# MCU.net
KiCad netlist of a schematic drawn in Altium Designer
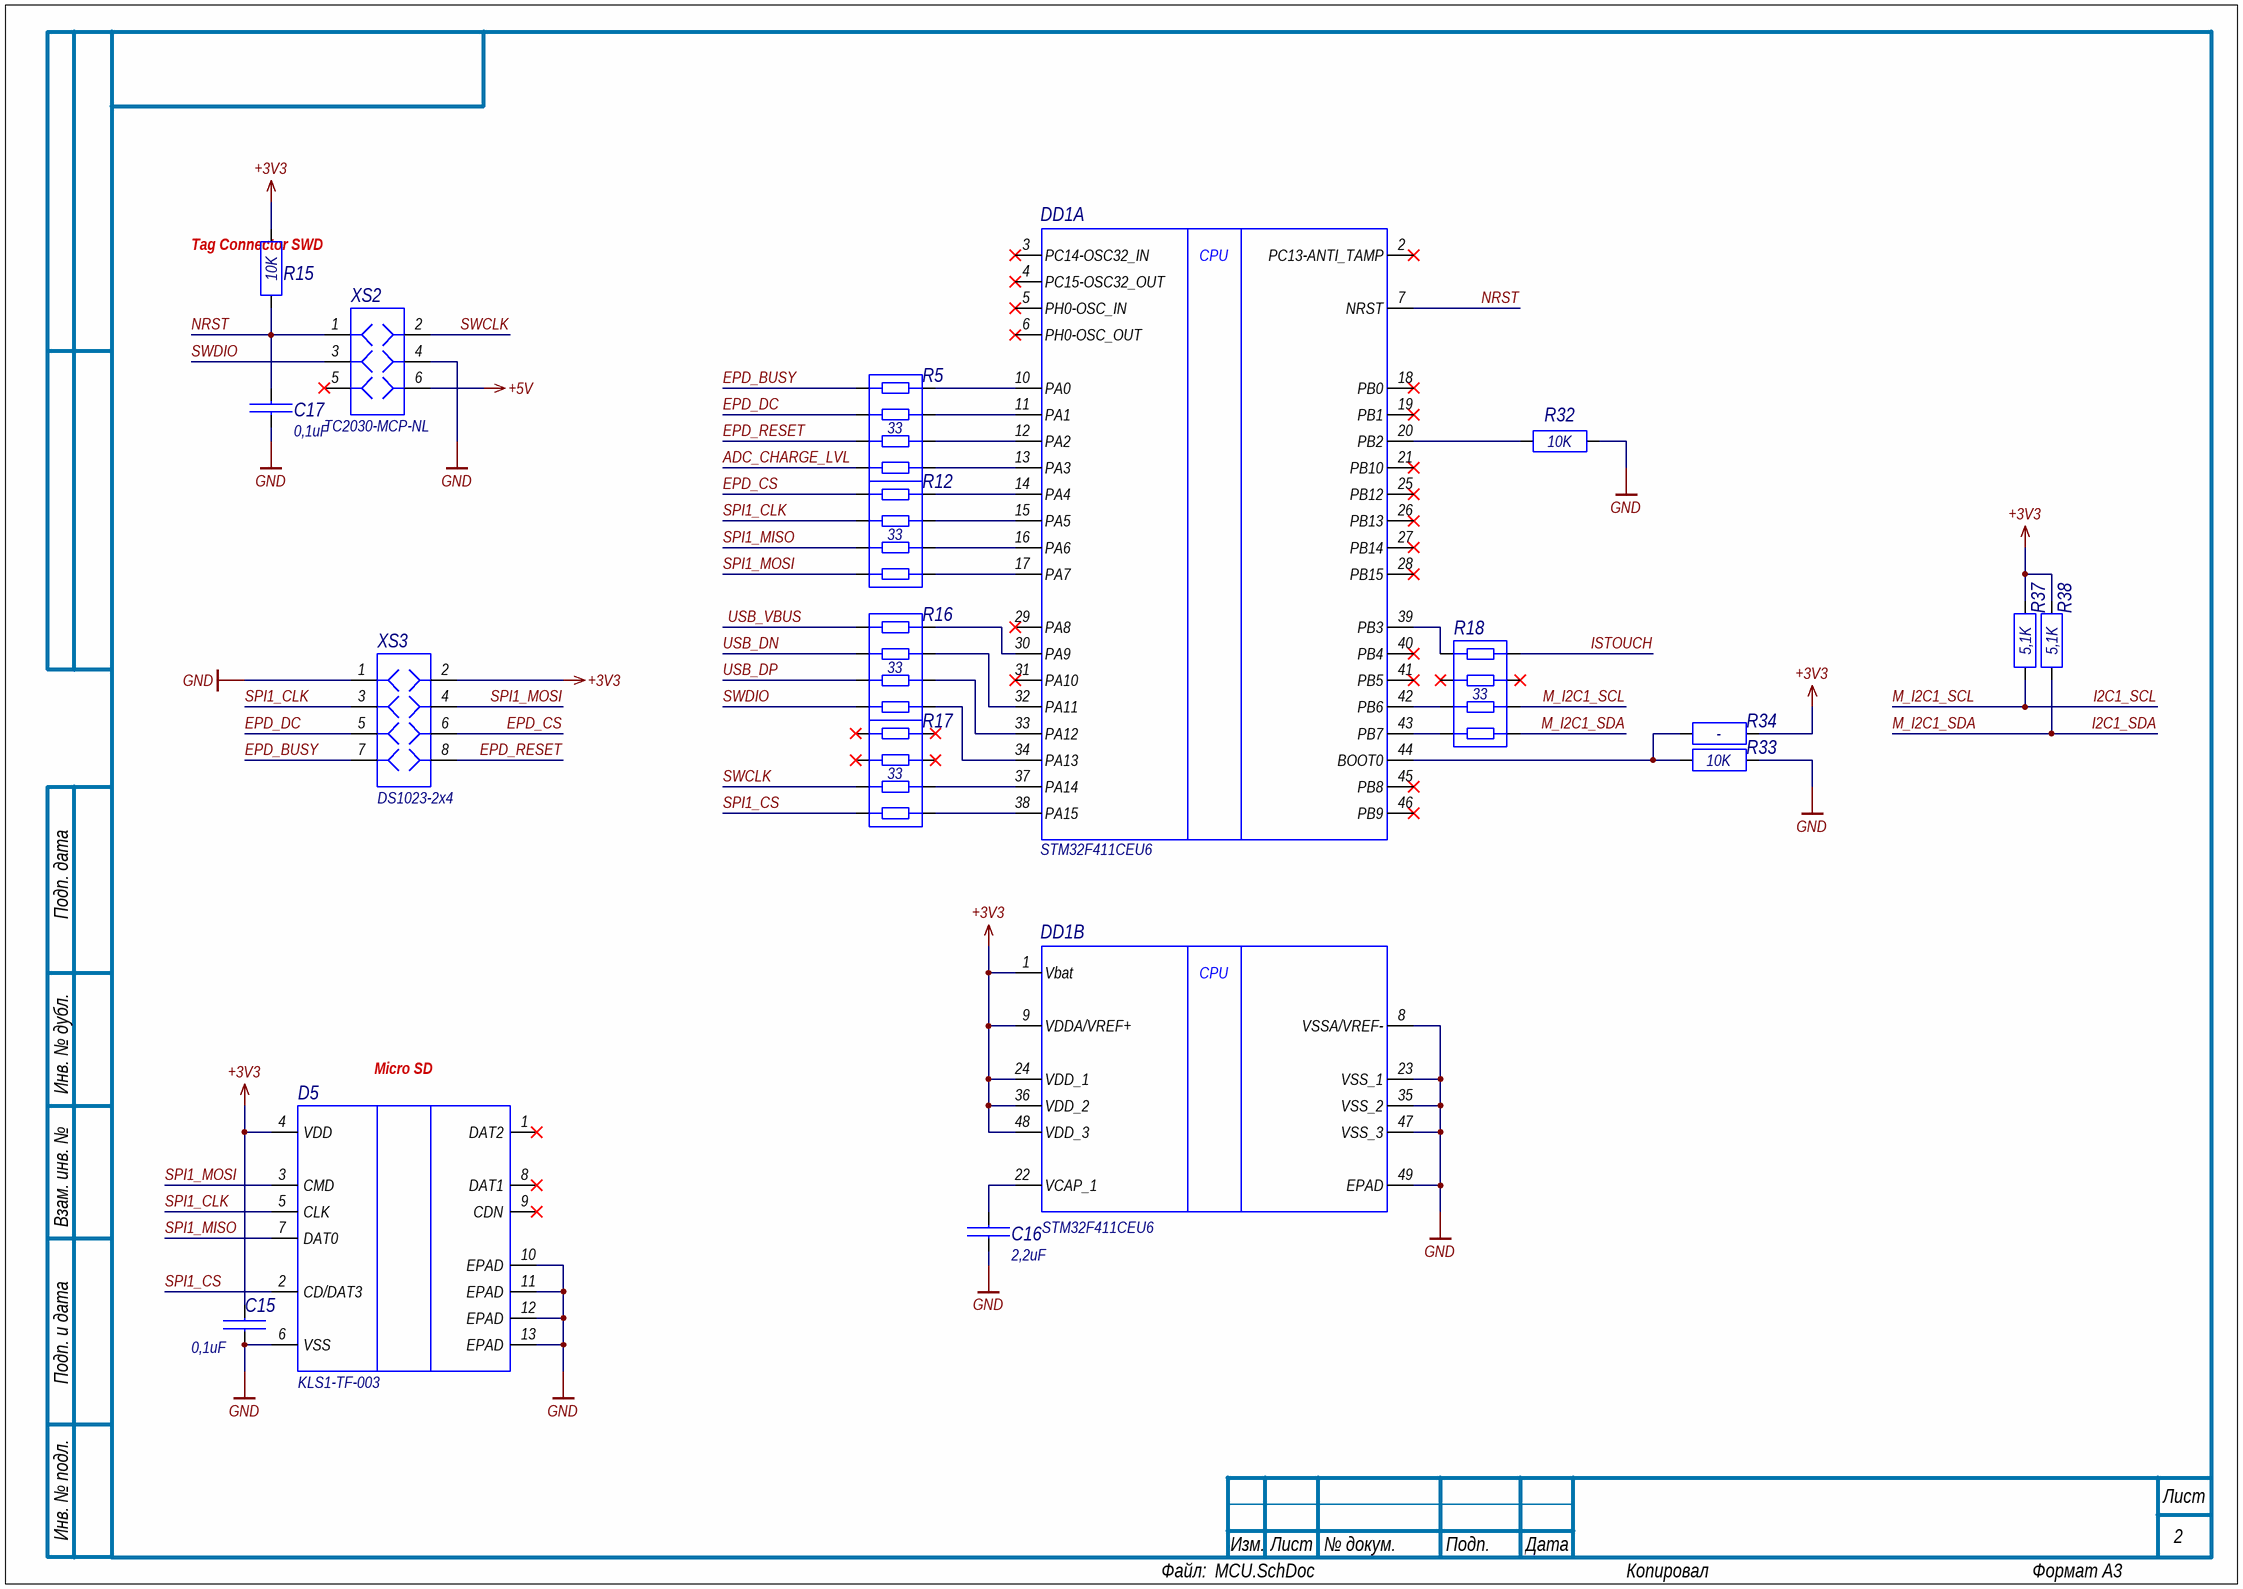
[diagram p0: MCU.SchDoc]

(export (version "E")
  (design (tool "Eeschema 10.0.6"))
  (components
    (comp (ref "C15")
      (value "0,1uF")
      (footprint "CAP_0603")
      (description "Ceramic Capacitor SMD_0603 X7R")
      (fields (field (name "VOLTAGE") "25V") (field (name "PART NUMBER") "CAP_CER_0603_104_25_10_X7R"))
      (libsource (lib "myLib_ESKD") (part "CAPACITOR"))
    )
    (comp (ref "C16")
      (value "2,2uF")
      (footprint "CAP_0603")
      (description "Ceramic Capacitor SMD_0603 X5R")
      (fields (field (name "VOLTAGE") "10V") (field (name "PART NUMBER") "CAP_CER_0603_225_10_10_X5R"))
      (libsource (lib "myLib_ESKD") (part "CAPACITOR"))
    )
    (comp (ref "C17")
      (value "0,1uF")
      (footprint "CAP_0603")
      (description "Ceramic Capacitor SMD_0603 X7R")
      (fields (field (name "VOLTAGE") "25V") (field (name "PART NUMBER") "CAP_CER_0603_104_25_10_X7R"))
      (libsource (lib "myLib_ESKD") (part "CAPACITOR"))
    )
    (comp (ref "D5")
      (value "KLS1-TF-003")
      (footprint "KLS1-TF-003")
      (description "microSD Card Connector")
      (fields (field (name "MANUFACTURER") "KLS"))
      (libsource (lib "myLib_ESKD") (part "KLS1-TF-003"))
    )
    (comp (ref "DD1")
      (value "STM32F411CEU6")
      (footprint "UFQFPN48")
      (fields
        (field (name "MOUSER PART NUMBER") "511-STM32F411CEU6")
        (field (name "MANUFACTURER") "STMicroelectronics")
      )
      (libsource (lib "myLib_ESKD") (part "STM32F411CEU6"))
    )
    (comp (ref "R5")
      (value "33")
      (footprint "RES_ARRAY_0804_CONVEX")
      (description "CAY10 Series - Chip Resistor Array")
      (fields (field (name "PART NUMBER") "RES_ARR_CAY10_33R") (field (name "TOLERANCE") "5%"))
      (libsource (lib "myLib_ESKD") (part "RESISTOR_ARRAY"))
    )
    (comp (ref "R12")
      (value "33")
      (footprint "RES_ARRAY_0804_CONVEX")
      (description "CAY10 Series - Chip Resistor Array")
      (fields (field (name "PART NUMBER") "RES_ARR_CAY10_33R") (field (name "TOLERANCE") "5%"))
      (libsource (lib "myLib_ESKD") (part "RESISTOR_ARRAY"))
    )
    (comp (ref "R15")
      (value "10K")
      (footprint "RES_0603")
      (description "Resistor fixed SMD_0603 5%")
      (fields (field (name "POWER") "100mW") (field (name "PART NUMBER") "RES_SMD_0603_10K_5%"))
      (libsource (lib "myLib_ESKD") (part "RESISTOR"))
    )
    (comp (ref "R16")
      (value "33")
      (footprint "RES_ARRAY_0804_CONVEX")
      (description "CAY10 Series - Chip Resistor Array")
      (fields (field (name "PART NUMBER") "RES_ARR_CAY10_33R") (field (name "TOLERANCE") "5%"))
      (libsource (lib "myLib_ESKD") (part "RESISTOR_ARRAY"))
    )
    (comp (ref "R17")
      (value "33")
      (footprint "RES_ARRAY_0804_CONVEX")
      (description "CAY10 Series - Chip Resistor Array")
      (fields (field (name "PART NUMBER") "RES_ARR_CAY10_33R") (field (name "TOLERANCE") "5%"))
      (libsource (lib "myLib_ESKD") (part "RESISTOR_ARRAY"))
    )
    (comp (ref "R18")
      (value "33")
      (footprint "RES_ARRAY_0804_CONVEX")
      (description "CAY10 Series - Chip Resistor Array")
      (fields (field (name "PART NUMBER") "RES_ARR_CAY10_33R") (field (name "TOLERANCE") "5%"))
      (libsource (lib "myLib_ESKD") (part "RESISTOR_ARRAY"))
    )
    (comp (ref "R32")
      (value "10K")
      (footprint "RES_0603")
      (description "Resistor fixed SMD_0603 5%")
      (fields (field (name "POWER") "100mW") (field (name "PART NUMBER") "RES_SMD_0603_10K_5%"))
      (libsource (lib "myLib_ESKD") (part "RESISTOR"))
    )
    (comp (ref "R33")
      (value "10K")
      (footprint "RES_0603")
      (description "Resistor fixed SMD_0603 5%")
      (fields (field (name "POWER") "100mW") (field (name "PART NUMBER") "RES_SMD_0603_10K_5%"))
      (libsource (lib "myLib_ESKD") (part "RESISTOR"))
    )
    (comp (ref "R34")
      (value "-")
      (footprint "RES_0603")
      (description "Resistor fixed SMD_0603 5%")
      (fields (field (name "POWER") "100mW") (field (name "PART NUMBER") "RES_SMD_0603_10K_5%"))
      (libsource (lib "myLib_ESKD") (part "RESISTOR"))
    )
    (comp (ref "R37")
      (value "5,1K")
      (footprint "RES_0603")
      (description "Resistor fixed SMD_0603 5%")
      (fields (field (name "POWER") "100mW") (field (name "PART NUMBER") "RES_SMD_0603_5K1_5%"))
      (libsource (lib "myLib_ESKD") (part "RESISTOR"))
    )
    (comp (ref "R38")
      (value "5,1K")
      (footprint "RES_0603")
      (description "Resistor fixed SMD_0603 5%")
      (fields (field (name "POWER") "100mW") (field (name "PART NUMBER") "RES_SMD_0603_5K1_5%"))
      (libsource (lib "myLib_ESKD") (part "RESISTOR"))
    )
    (comp (ref "XS2")
      (value "TC2030-MCP-NL")
      (footprint "TC2030-MCP-NL")
      (description "Tag connector 2x3")
      (fields (field (name "MANUFACTURER") "Tag Connect") (field (name "Comment") "HEADER-3x2-F"))
      (libsource (lib "myLib_ESKD") (part "HEADER-3x2-F"))
    )
    (comp (ref "XS3")
      (value "DS1023-2x4")
      (footprint "PBD-8")
      (description "Female Socket Header Through Hole 8 (2x4) Position 0.100\" (2.54mm)")
      (fields (field (name "PART NUMBER") "PBD-8") (field (name "MANUFACTURER") "Connfly"))
      (libsource (lib "myLib_ESKD") (part "HEADER-4x2-F"))
    )
  )
  (nets
    (net (code "1") (name "+3V3") (class "Default")
      (node (ref "C15") (pin "1") (pinfunction "1_1") (pintype "passive"))
      (node (ref "D5") (pin "4") (pinfunction "VDD_4") (pintype "passive"))
      (node (ref "DD1") (pin "1") (pinfunction "Vbat_1") (pintype "passive"))
      (node (ref "DD1") (pin "24") (pinfunction "VDD_1_24") (pintype "passive"))
      (node (ref "DD1") (pin "36") (pinfunction "VDD_2_36") (pintype "passive"))
      (node (ref "DD1") (pin "48") (pinfunction "VDD_3_48") (pintype "passive"))
      (node (ref "DD1") (pin "9") (pinfunction "VDDA/VREF+_9") (pintype "passive"))
      (node (ref "R15") (pin "2") (pinfunction "2_2") (pintype "passive"))
      (node (ref "R34") (pin "2") (pinfunction "2_2") (pintype "passive"))
      (node (ref "R37") (pin "2") (pinfunction "2_2") (pintype "passive"))
      (node (ref "R38") (pin "2") (pinfunction "2_2") (pintype "passive"))
      (node (ref "XS3") (pin "2") (pinfunction "2_2") (pintype "passive"))
    )
    (net (code "2") (name "+5V") (class "Default")
      (node (ref "XS2") (pin "6") (pinfunction "6_6") (pintype "passive"))
    )
    (net (code "3") (name "/ADC_CHARGE_LVL") (class "Default")
      (node (ref "R5") (pin "4") (pinfunction "4_4") (pintype "passive"))
    )
    (net (code "4") (name "/EPD_BUSY") (class "Default")
      (node (ref "R5") (pin "1") (pinfunction "1_1") (pintype "passive"))
      (node (ref "XS3") (pin "7") (pinfunction "7_7") (pintype "passive"))
    )
    (net (code "5") (name "/EPD_CS") (class "Default")
      (node (ref "R12") (pin "1") (pinfunction "1_1") (pintype "passive"))
      (node (ref "XS3") (pin "6") (pinfunction "6_6") (pintype "passive"))
    )
    (net (code "6") (name "/EPD_DC") (class "Default")
      (node (ref "R5") (pin "2") (pinfunction "2_2") (pintype "passive"))
      (node (ref "XS3") (pin "5") (pinfunction "5_5") (pintype "passive"))
    )
    (net (code "7") (name "/EPD_RESET") (class "Default")
      (node (ref "R5") (pin "3") (pinfunction "3_3") (pintype "passive"))
      (node (ref "XS3") (pin "8") (pinfunction "8_8") (pintype "passive"))
    )
    (net (code "8") (name "/I2C1_SCL") (class "Default")
      (node (ref "R18") (pin "7") (pinfunction "7_7") (pintype "passive"))
      (node (ref "R37") (pin "1") (pinfunction "1_1") (pintype "passive"))
    )
    (net (code "9") (name "/I2C1_SDA") (class "Default")
      (node (ref "R18") (pin "8") (pinfunction "8_8") (pintype "passive"))
      (node (ref "R38") (pin "1") (pinfunction "1_1") (pintype "passive"))
    )
    (net (code "10") (name "/ISTOUCH") (class "Default")
      (node (ref "R18") (pin "5") (pinfunction "5_5") (pintype "passive"))
    )
    (net (code "11") (name "/NRST") (class "Default")
      (node (ref "C17") (pin "1") (pinfunction "1_1") (pintype "passive"))
      (node (ref "DD1") (pin "7") (pinfunction "NRST_7") (pintype "passive"))
      (node (ref "R15") (pin "1") (pinfunction "1_1") (pintype "passive"))
      (node (ref "XS2") (pin "1") (pinfunction "1_1") (pintype "passive"))
    )
    (net (code "12") (name "/SPI1_CLK") (class "Default")
      (node (ref "D5") (pin "5") (pinfunction "CLK_5") (pintype "passive"))
      (node (ref "R12") (pin "2") (pinfunction "2_2") (pintype "passive"))
      (node (ref "XS3") (pin "3") (pinfunction "3_3") (pintype "passive"))
    )
    (net (code "13") (name "/SPI1_CS") (class "Default")
      (node (ref "D5") (pin "2") (pinfunction "CD/DAT3_2") (pintype "passive"))
      (node (ref "R17") (pin "4") (pinfunction "4_4") (pintype "passive"))
    )
    (net (code "14") (name "/SPI1_MISO") (class "Default")
      (node (ref "D5") (pin "7") (pinfunction "DAT0_7") (pintype "passive"))
      (node (ref "R12") (pin "3") (pinfunction "3_3") (pintype "passive"))
    )
    (net (code "15") (name "/SPI1_MOSI") (class "Default")
      (node (ref "D5") (pin "3") (pinfunction "CMD_3") (pintype "passive"))
      (node (ref "R12") (pin "4") (pinfunction "4_4") (pintype "passive"))
      (node (ref "XS3") (pin "4") (pinfunction "4_4") (pintype "passive"))
    )
    (net (code "16") (name "/SWCLK") (class "Default")
      (node (ref "R17") (pin "3") (pinfunction "3_3") (pintype "passive"))
      (node (ref "XS2") (pin "2") (pinfunction "2_2") (pintype "passive"))
    )
    (net (code "17") (name "/SWDIO") (class "Default")
      (node (ref "R16") (pin "4") (pinfunction "4_4") (pintype "passive"))
      (node (ref "XS2") (pin "3") (pinfunction "3_3") (pintype "passive"))
    )
    (net (code "18") (name "/USB_DN") (class "Default")
      (node (ref "R16") (pin "2") (pinfunction "2_2") (pintype "passive"))
    )
    (net (code "19") (name "/USB_DP") (class "Default")
      (node (ref "R16") (pin "3") (pinfunction "3_3") (pintype "passive"))
    )
    (net (code "20") (name "/USB_VBUS") (class "Default")
      (node (ref "R16") (pin "1") (pinfunction "1_1") (pintype "passive"))
    )
    (net (code "21") (name "GND") (class "Default")
      (node (ref "C15") (pin "2") (pinfunction "2_2") (pintype "passive"))
      (node (ref "C16") (pin "2") (pinfunction "2_2") (pintype "passive"))
      (node (ref "C17") (pin "2") (pinfunction "2_2") (pintype "passive"))
      (node (ref "D5") (pin "10") (pinfunction "EPAD_10") (pintype "passive"))
      (node (ref "D5") (pin "11") (pinfunction "EPAD_11") (pintype "passive"))
      (node (ref "D5") (pin "12") (pinfunction "EPAD_12") (pintype "passive"))
      (node (ref "D5") (pin "13") (pinfunction "EPAD_13") (pintype "passive"))
      (node (ref "D5") (pin "6") (pinfunction "VSS_6") (pintype "passive"))
      (node (ref "DD1") (pin "23") (pinfunction "VSS_1_23") (pintype "passive"))
      (node (ref "DD1") (pin "35") (pinfunction "VSS_2_35") (pintype "passive"))
      (node (ref "DD1") (pin "47") (pinfunction "VSS_3_47") (pintype "passive"))
      (node (ref "DD1") (pin "49") (pinfunction "EPAD_49") (pintype "passive"))
      (node (ref "DD1") (pin "8") (pinfunction "VSSA/VREF-_8") (pintype "passive"))
      (node (ref "R32") (pin "2") (pinfunction "2_2") (pintype "passive"))
      (node (ref "R33") (pin "2") (pinfunction "2_2") (pintype "passive"))
      (node (ref "XS2") (pin "4") (pinfunction "4_4") (pintype "passive"))
      (node (ref "XS3") (pin "1") (pinfunction "1_1") (pintype "passive"))
    )
    (net (code "22") (name "Net-(DD1A-BOOT0)") (class "Default")
      (node (ref "DD1") (pin "44") (pinfunction "BOOT0_44") (pintype "passive"))
      (node (ref "R33") (pin "1") (pinfunction "1_1") (pintype "passive"))
      (node (ref "R34") (pin "1") (pinfunction "1_1") (pintype "passive"))
    )
    (net (code "23") (name "Net-(DD1A-PA0)") (class "Default")
      (node (ref "DD1") (pin "10") (pinfunction "PA0_10") (pintype "passive"))
      (node (ref "R5") (pin "8") (pinfunction "8_8") (pintype "passive"))
    )
    (net (code "24") (name "Net-(DD1A-PA1)") (class "Default")
      (node (ref "DD1") (pin "11") (pinfunction "PA1_11") (pintype "passive"))
      (node (ref "R5") (pin "7") (pinfunction "7_7") (pintype "passive"))
    )
    (net (code "25") (name "Net-(DD1A-PA2)") (class "Default")
      (node (ref "DD1") (pin "12") (pinfunction "PA2_12") (pintype "passive"))
      (node (ref "R5") (pin "6") (pinfunction "6_6") (pintype "passive"))
    )
    (net (code "26") (name "Net-(DD1A-PA3)") (class "Default")
      (node (ref "DD1") (pin "13") (pinfunction "PA3_13") (pintype "passive"))
      (node (ref "R5") (pin "5") (pinfunction "5_5") (pintype "passive"))
    )
    (net (code "27") (name "Net-(DD1A-PA4)") (class "Default")
      (node (ref "DD1") (pin "14") (pinfunction "PA4_14") (pintype "passive"))
      (node (ref "R12") (pin "8") (pinfunction "8_8") (pintype "passive"))
    )
    (net (code "28") (name "Net-(DD1A-PA5)") (class "Default")
      (node (ref "DD1") (pin "15") (pinfunction "PA5_15") (pintype "passive"))
      (node (ref "R12") (pin "7") (pinfunction "7_7") (pintype "passive"))
    )
    (net (code "29") (name "Net-(DD1A-PA6)") (class "Default")
      (node (ref "DD1") (pin "16") (pinfunction "PA6_16") (pintype "passive"))
      (node (ref "R12") (pin "6") (pinfunction "6_6") (pintype "passive"))
    )
    (net (code "30") (name "Net-(DD1A-PA7)") (class "Default")
      (node (ref "DD1") (pin "17") (pinfunction "PA7_17") (pintype "passive"))
      (node (ref "R12") (pin "5") (pinfunction "5_5") (pintype "passive"))
    )
    (net (code "31") (name "Net-(DD1A-PA9)") (class "Default")
      (node (ref "DD1") (pin "30") (pinfunction "PA9_30") (pintype "passive"))
      (node (ref "R16") (pin "8") (pinfunction "8_8") (pintype "passive"))
    )
    (net (code "32") (name "Net-(DD1A-PA11)") (class "Default")
      (node (ref "DD1") (pin "32") (pinfunction "PA11_32") (pintype "passive"))
      (node (ref "R16") (pin "7") (pinfunction "7_7") (pintype "passive"))
    )
    (net (code "33") (name "Net-(DD1A-PA12)") (class "Default")
      (node (ref "DD1") (pin "33") (pinfunction "PA12_33") (pintype "passive"))
      (node (ref "R16") (pin "6") (pinfunction "6_6") (pintype "passive"))
    )
    (net (code "34") (name "Net-(DD1A-PA13)") (class "Default")
      (node (ref "DD1") (pin "34") (pinfunction "PA13_34") (pintype "passive"))
      (node (ref "R16") (pin "5") (pinfunction "5_5") (pintype "passive"))
    )
    (net (code "35") (name "Net-(DD1A-PA14)") (class "Default")
      (node (ref "DD1") (pin "37") (pinfunction "PA14_37") (pintype "passive"))
      (node (ref "R17") (pin "6") (pinfunction "6_6") (pintype "passive"))
    )
    (net (code "36") (name "Net-(DD1A-PA15)") (class "Default")
      (node (ref "DD1") (pin "38") (pinfunction "PA15_38") (pintype "passive"))
      (node (ref "R17") (pin "5") (pinfunction "5_5") (pintype "passive"))
    )
    (net (code "37") (name "Net-(DD1A-PB2)") (class "Default")
      (node (ref "DD1") (pin "20") (pinfunction "PB2_20") (pintype "passive"))
      (node (ref "R32") (pin "1") (pinfunction "1_1") (pintype "passive"))
    )
    (net (code "38") (name "Net-(DD1A-PB3)") (class "Default")
      (node (ref "DD1") (pin "39") (pinfunction "PB3_39") (pintype "passive"))
      (node (ref "R18") (pin "4") (pinfunction "4_4") (pintype "passive"))
    )
    (net (code "39") (name "Net-(DD1A-PB6)") (class "Default")
      (node (ref "DD1") (pin "42") (pinfunction "PB6_42") (pintype "passive"))
      (node (ref "R18") (pin "2") (pinfunction "2_2") (pintype "passive"))
    )
    (net (code "40") (name "Net-(DD1A-PB7)") (class "Default")
      (node (ref "DD1") (pin "43") (pinfunction "PB7_43") (pintype "passive"))
      (node (ref "R18") (pin "1") (pinfunction "1_1") (pintype "passive"))
    )
    (net (code "41") (name "Net-(DD1B-VCAP_1)") (class "Default")
      (node (ref "C16") (pin "1") (pinfunction "1_1") (pintype "passive"))
      (node (ref "DD1") (pin "22") (pinfunction "VCAP_1_22") (pintype "passive"))
    )
    (net (code "42") (name "unconnected-(D5-CDN-Pad9)") (class "Default")
      (node (ref "D5") (pin "9") (pinfunction "CDN_9") (pintype "passive+no_connect"))
    )
    (net (code "43") (name "unconnected-(D5-DAT1-Pad8)") (class "Default")
      (node (ref "D5") (pin "8") (pinfunction "DAT1_8") (pintype "passive+no_connect"))
    )
    (net (code "44") (name "unconnected-(D5-DAT2-Pad1)") (class "Default")
      (node (ref "D5") (pin "1") (pinfunction "DAT2_1") (pintype "passive+no_connect"))
    )
    (net (code "45") (name "unconnected-(DD1A-PA8-Pad29)") (class "Default")
      (node (ref "DD1") (pin "29") (pinfunction "PA8_29") (pintype "passive+no_connect"))
    )
    (net (code "46") (name "unconnected-(DD1A-PA10-Pad31)") (class "Default")
      (node (ref "DD1") (pin "31") (pinfunction "PA10_31") (pintype "passive+no_connect"))
    )
    (net (code "47") (name "unconnected-(DD1A-PB0-Pad18)") (class "Default")
      (node (ref "DD1") (pin "18") (pinfunction "PB0_18") (pintype "passive+no_connect"))
    )
    (net (code "48") (name "unconnected-(DD1A-PB1-Pad19)") (class "Default")
      (node (ref "DD1") (pin "19") (pinfunction "PB1_19") (pintype "passive+no_connect"))
    )
    (net (code "49") (name "unconnected-(DD1A-PB4-Pad40)") (class "Default")
      (node (ref "DD1") (pin "40") (pinfunction "PB4_40") (pintype "passive+no_connect"))
    )
    (net (code "50") (name "unconnected-(DD1A-PB5-Pad41)") (class "Default")
      (node (ref "DD1") (pin "41") (pinfunction "PB5_41") (pintype "passive+no_connect"))
    )
    (net (code "51") (name "unconnected-(DD1A-PB8-Pad45)") (class "Default")
      (node (ref "DD1") (pin "45") (pinfunction "PB8_45") (pintype "passive+no_connect"))
    )
    (net (code "52") (name "unconnected-(DD1A-PB9-Pad46)") (class "Default")
      (node (ref "DD1") (pin "46") (pinfunction "PB9_46") (pintype "passive+no_connect"))
    )
    (net (code "53") (name "unconnected-(DD1A-PB10-Pad21)") (class "Default")
      (node (ref "DD1") (pin "21") (pinfunction "PB10_21") (pintype "passive+no_connect"))
    )
    (net (code "54") (name "unconnected-(DD1A-PB12-Pad25)") (class "Default")
      (node (ref "DD1") (pin "25") (pinfunction "PB12_25") (pintype "passive+no_connect"))
    )
    (net (code "55") (name "unconnected-(DD1A-PB13-Pad26)") (class "Default")
      (node (ref "DD1") (pin "26") (pinfunction "PB13_26") (pintype "passive+no_connect"))
    )
    (net (code "56") (name "unconnected-(DD1A-PB14-Pad27)") (class "Default")
      (node (ref "DD1") (pin "27") (pinfunction "PB14_27") (pintype "passive+no_connect"))
    )
    (net (code "57") (name "unconnected-(DD1A-PB15-Pad28)") (class "Default")
      (node (ref "DD1") (pin "28") (pinfunction "PB15_28") (pintype "passive+no_connect"))
    )
    (net (code "58") (name "unconnected-(DD1A-PC13-ANTI_TAMP-Pad2)") (class "Default")
      (node (ref "DD1") (pin "2") (pinfunction "PC13-ANTI_TAMP_2") (pintype "passive+no_connect"))
    )
    (net (code "59") (name "unconnected-(DD1A-PC14-OSC32_IN-Pad3)") (class "Default")
      (node (ref "DD1") (pin "3") (pinfunction "PC14-OSC32_IN_3") (pintype "passive+no_connect"))
    )
    (net (code "60") (name "unconnected-(DD1A-PC15-OSC32_OUT-Pad4)") (class "Default")
      (node (ref "DD1") (pin "4") (pinfunction "PC15-OSC32_OUT_4") (pintype "passive+no_connect"))
    )
    (net (code "61") (name "unconnected-(DD1A-PH0-OSC_IN-Pad5)") (class "Default")
      (node (ref "DD1") (pin "5") (pinfunction "PH0-OSC_IN_5") (pintype "passive+no_connect"))
    )
    (net (code "62") (name "unconnected-(DD1A-PH0-OSC_OUT-Pad6)") (class "Default")
      (node (ref "DD1") (pin "6") (pinfunction "PH0-OSC_OUT_6") (pintype "passive+no_connect"))
    )
    (net (code "63") (name "unconnected-(R17-Pad1)") (class "Default")
      (node (ref "R17") (pin "1") (pinfunction "1_1") (pintype "passive+no_connect"))
    )
    (net (code "64") (name "unconnected-(R17-Pad2)") (class "Default")
      (node (ref "R17") (pin "2") (pinfunction "2_2") (pintype "passive+no_connect"))
    )
    (net (code "65") (name "unconnected-(R17-Pad7)") (class "Default")
      (node (ref "R17") (pin "7") (pinfunction "7_7") (pintype "passive+no_connect"))
    )
    (net (code "66") (name "unconnected-(R17-Pad8)") (class "Default")
      (node (ref "R17") (pin "8") (pinfunction "8_8") (pintype "passive+no_connect"))
    )
    (net (code "67") (name "unconnected-(R18-Pad3)") (class "Default")
      (node (ref "R18") (pin "3") (pinfunction "3_3") (pintype "passive+no_connect"))
    )
    (net (code "68") (name "unconnected-(R18-Pad6)") (class "Default")
      (node (ref "R18") (pin "6") (pinfunction "6_6") (pintype "passive+no_connect"))
    )
    (net (code "69") (name "unconnected-(XS2-Pad5)") (class "Default")
      (node (ref "XS2") (pin "5") (pinfunction "5_5") (pintype "passive+no_connect"))
    )
  )
)
